# dimmer.net
KiCad netlist of a schematic drawn in EAGLE
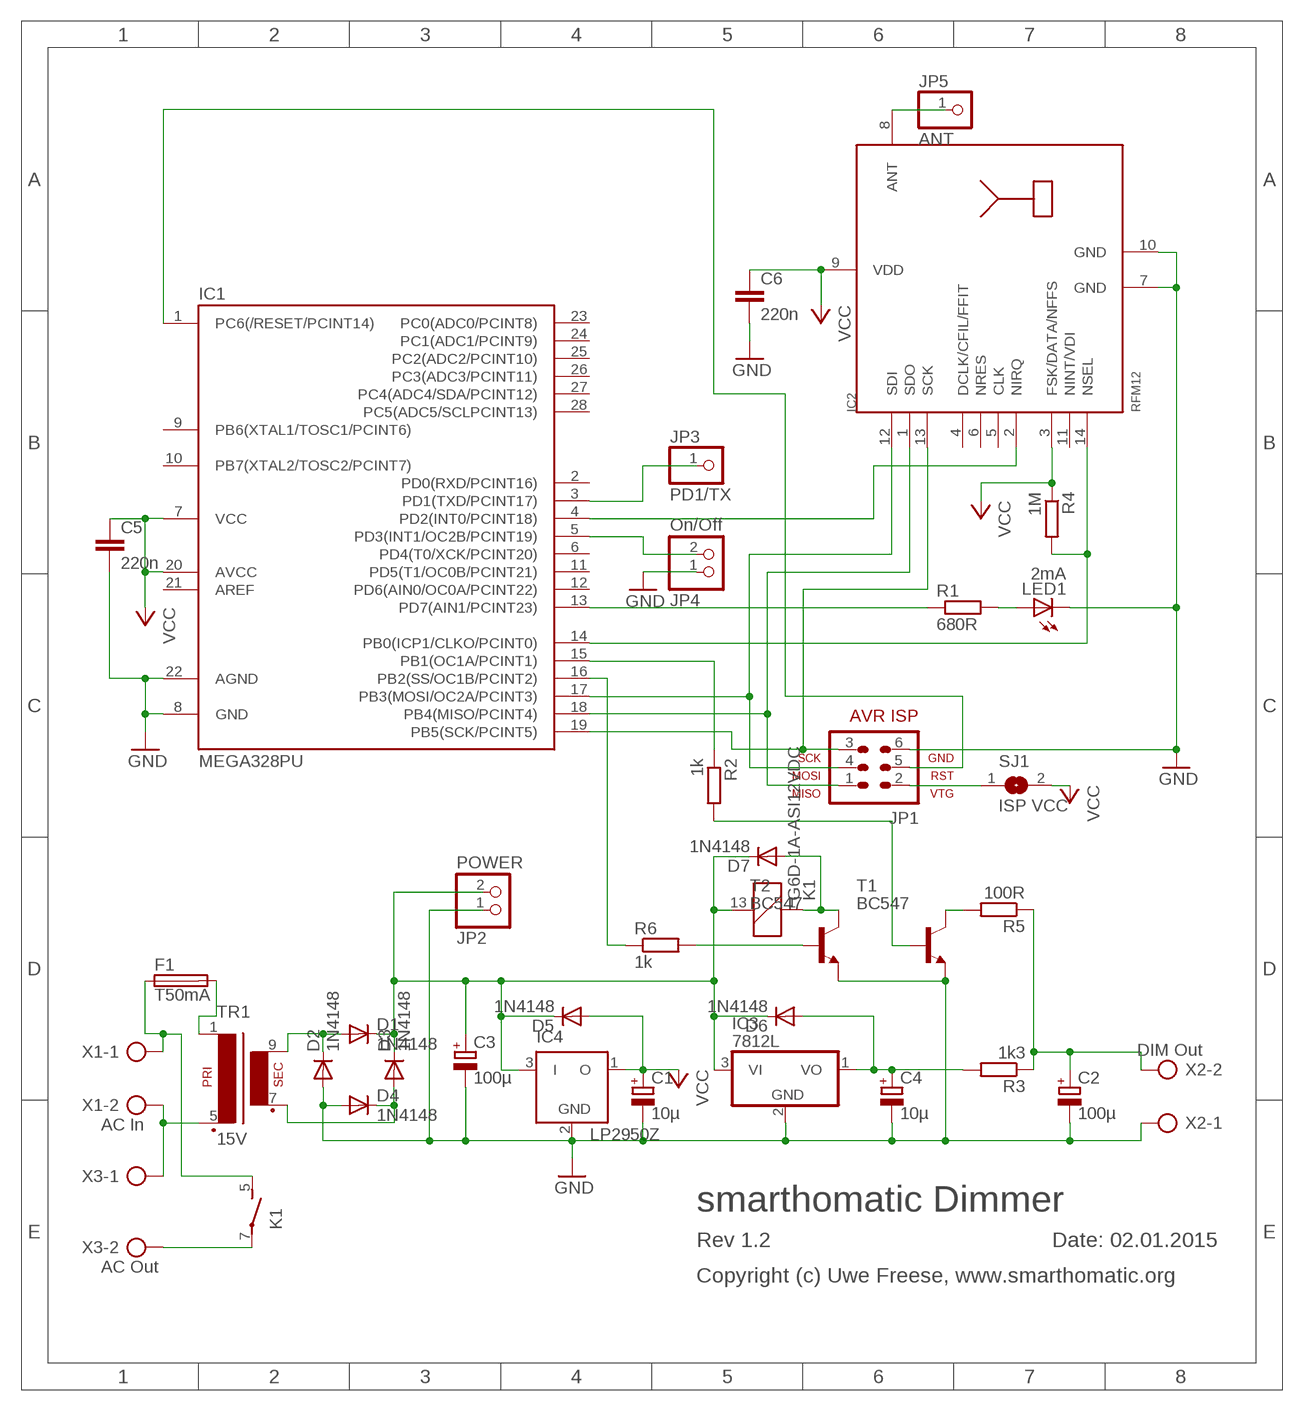
[diagram p0: schematic, sheet 1]

(export (version "E")
  (design (tool "Eeschema 10.0.6"))
  (components
    (comp (ref "C1")
      (value "10µ")
      (footprint "eagle-import:E1,8-4")
      (libsource (lib "eagle-import") (part "CPOL-EUE1.8-4"))
    )
    (comp (ref "C2")
      (value "100µ")
      (footprint "eagle-import:E1,8-4")
      (libsource (lib "eagle-import") (part "CPOL-EUE1.8-4"))
    )
    (comp (ref "C3")
      (value "100µ")
      (footprint "eagle-import:E1,8-4")
      (libsource (lib "eagle-import") (part "CPOL-EUE1.8-4"))
    )
    (comp (ref "C4")
      (value "10µ")
      (footprint "eagle-import:E1,8-4")
      (libsource (lib "eagle-import") (part "CPOL-EUE1.8-4"))
    )
    (comp (ref "C5")
      (value "220n")
      (footprint "eagle-import:C2.5-3")
      (libsource (lib "eagle-import") (part "C2,5-3"))
    )
    (comp (ref "C6")
      (value "220n")
      (footprint "eagle-import:C2.5-3")
      (libsource (lib "eagle-import") (part "C2,5-3"))
    )
    (comp (ref "D1")
      (value "1N4148")
      (footprint "eagle-import:DO35-7")
      (libsource (lib "eagle-import") (part "1N4148DO35-7"))
    )
    (comp (ref "D2")
      (value "1N4148")
      (footprint "eagle-import:DO35-7")
      (libsource (lib "eagle-import") (part "1N4148DO35-7"))
    )
    (comp (ref "D3")
      (value "1N4148")
      (footprint "eagle-import:DO35-7")
      (libsource (lib "eagle-import") (part "1N4148DO35-7"))
    )
    (comp (ref "D4")
      (value "1N4148")
      (footprint "eagle-import:DO35-7")
      (libsource (lib "eagle-import") (part "1N4148DO35-7"))
    )
    (comp (ref "D5")
      (value "1N4148")
      (footprint "eagle-import:DO35-7")
      (libsource (lib "eagle-import") (part "1N4148DO35-7"))
    )
    (comp (ref "D6")
      (value "1N4148")
      (footprint "eagle-import:DO35-7")
      (libsource (lib "eagle-import") (part "1N4148DO35-7"))
    )
    (comp (ref "D7")
      (value "1N4148")
      (footprint "eagle-import:DO35-7")
      (libsource (lib "eagle-import") (part "1N4148DO35-7"))
    )
    (comp (ref "F1")
      (value "T50mA")
      (footprint "eagle-import:SH22,5")
      (fields (field (name "MF") "SCHURTER") (field (name "MPN") "0031.8201"))
      (libsource (lib "eagle-import") (part "SH22,5"))
    )
    (comp (ref "IC1")
      (value "MEGA328PU")
      (footprint "eagle-import:DIL28-3")
      (libsource (lib "eagle-import") (part "MEGA48/88/168-PU"))
    )
    (comp (ref "IC2")
      (value "RFM12")
      (footprint "eagle-import:RFM")
      (libsource (lib "eagle-import") (part "RFM12"))
    )
    (comp (ref "IC3")
      (value "7812L")
      (footprint "eagle-import:TO92")
      (libsource (lib "eagle-import") (part "78L12"))
    )
    (comp (ref "IC4")
      (value "LP2950Z")
      (footprint "eagle-import:TO92")
      (libsource (lib "eagle-import") (part "LP2950Z"))
    )
    (comp (ref "JP1")
      (value "AVR-ISP-6")
      (footprint "eagle-import:AVR-ISP-6")
      (libsource (lib "eagle-import") (part "AVR-ISP-6"))
    )
    (comp (ref "JP2")
      (value "POWER")
      (footprint "eagle-import:1X02")
      (libsource (lib "eagle-import") (part "PINHD-1X2"))
    )
    (comp (ref "JP3")
      (value "PD1/TX")
      (footprint "eagle-import:1X01")
      (libsource (lib "eagle-import") (part "PINHD-1X1"))
    )
    (comp (ref "JP4")
      (value "On/Off")
      (footprint "eagle-import:1X02")
      (libsource (lib "eagle-import") (part "PINHD-1X2"))
    )
    (comp (ref "JP5")
      (value "ANT")
      (footprint "eagle-import:1X01")
      (libsource (lib "eagle-import") (part "PINHD-1X1"))
    )
    (comp (ref "K1")
      (value "G6D-1A-ASI12VDC")
      (footprint "eagle-import:G6D")
      (libsource (lib "eagle-import") (part "G6D?-1A-ASI12VDC"))
    )
    (comp (ref "LED1")
      (value "2mA")
      (footprint "eagle-import:LED3MM")
      (libsource (lib "eagle-import") (part "LED3MM"))
    )
    (comp (ref "R1")
      (value "680R")
      (footprint "eagle-import:0207_7")
      (libsource (lib "eagle-import") (part "R-EU_0207/7"))
    )
    (comp (ref "R2")
      (value "1k")
      (footprint "eagle-import:0207_7")
      (libsource (lib "eagle-import") (part "R-EU_0207/7"))
    )
    (comp (ref "R3")
      (value "1k3")
      (footprint "eagle-import:0207_7")
      (libsource (lib "eagle-import") (part "R-EU_0207/7"))
    )
    (comp (ref "R4")
      (value "1M")
      (footprint "eagle-import:0207_7")
      (libsource (lib "eagle-import") (part "R-EU_0207/7"))
    )
    (comp (ref "R5")
      (value "100R")
      (footprint "eagle-import:0207_7")
      (libsource (lib "eagle-import") (part "R-EU_0207/7"))
    )
    (comp (ref "R6")
      (value "1k")
      (footprint "eagle-import:0207_7")
      (libsource (lib "eagle-import") (part "R-EU_0207/7"))
    )
    (comp (ref "SJ1")
      (value "ISP VCC")
      (footprint "eagle-import:SJ")
      (libsource (lib "eagle-import") (part "SJ"))
    )
    (comp (ref "T1")
      (value "BC547")
      (footprint "eagle-import:TO92")
      (libsource (lib "eagle-import") (part "BC547"))
    )
    (comp (ref "T2")
      (value "BC547")
      (footprint "eagle-import:TO92")
      (libsource (lib "eagle-import") (part "BC547"))
    )
    (comp (ref "TR1")
      (value "15V")
      (footprint "eagle-import:EI30-1")
      (libsource (lib "eagle-import") (part "EI30-1"))
    )
    (comp (ref "X1")
      (value "AC In")
      (footprint "eagle-import:AK500_2")
      (libsource (lib "eagle-import") (part "AK500/2"))
    )
    (comp (ref "X2")
      (value "DIM Out")
      (footprint "eagle-import:AK500_2")
      (libsource (lib "eagle-import") (part "AK500/2"))
    )
    (comp (ref "X3")
      (value "AC Out")
      (footprint "eagle-import:AK500_2")
      (fields (field (name "OC_FARNELL") "unknown") (field (name "OC_NEWARK") "unknown"))
      (libsource (lib "eagle-import") (part "AK500/2"))
    )
  )
  (nets
    (net (code "1") (name "GND") (class "Default")
      (node (ref "C1") (pin "-") (pinfunction "-_-") (pintype "passive"))
      (node (ref "C2") (pin "-") (pinfunction "-_-") (pintype "passive"))
      (node (ref "C3") (pin "-") (pinfunction "-_-") (pintype "passive"))
      (node (ref "C4") (pin "-") (pinfunction "-_-") (pintype "passive"))
      (node (ref "C5") (pin "2") (pinfunction "2_2") (pintype "passive"))
      (node (ref "C6") (pin "2") (pinfunction "2_2") (pintype "passive"))
      (node (ref "D2") (pin "A") (pinfunction "A_A") (pintype "passive"))
      (node (ref "D4") (pin "A") (pinfunction "A_A") (pintype "passive"))
      (node (ref "IC1") (pin "22") (pinfunction "AGND_22") (pintype "power_in"))
      (node (ref "IC1") (pin "8") (pinfunction "GND_8") (pintype "power_in"))
      (node (ref "IC2") (pin "10") (pinfunction "GND_10") (pintype "power_in"))
      (node (ref "IC2") (pin "7") (pinfunction "GND_7") (pintype "power_in"))
      (node (ref "IC3") (pin "2") (pinfunction "GND_2") (pintype "passive"))
      (node (ref "IC4") (pin "2") (pinfunction "GND_2") (pintype "power_in"))
      (node (ref "JP1") (pin "6") (pinfunction "6_6") (pintype "passive"))
      (node (ref "JP2") (pin "1") (pinfunction "1_1") (pintype "passive"))
      (node (ref "JP4") (pin "1") (pinfunction "1_1") (pintype "passive"))
      (node (ref "LED1") (pin "K") (pinfunction "C_K") (pintype "passive"))
      (node (ref "T1") (pin "1") (pinfunction "E_1") (pintype "passive"))
      (node (ref "T2") (pin "1") (pinfunction "E_1") (pintype "passive"))
      (node (ref "X2") (pin "1") (pinfunction "KL_1") (pintype "passive"))
    )
    (net (code "2") (name "Net-(IC1-PB0(ICP1{slash}CLKO{slash}PCINT0))") (class "Default")
      (node (ref "IC1") (pin "14") (pinfunction "PB0(ICP1/CLKO/PCINT0)_14") (pintype "bidirectional"))
      (node (ref "IC2") (pin "14") (pinfunction "NSEL_14") (pintype "bidirectional"))
      (node (ref "R4") (pin "2") (pinfunction "2_2") (pintype "passive"))
    )
    (net (code "3") (name "Net-(IC1-PB1(OC1A{slash}PCINT1))") (class "Default")
      (node (ref "IC1") (pin "15") (pinfunction "PB1(OC1A/PCINT1)_15") (pintype "bidirectional"))
      (node (ref "R2") (pin "1") (pinfunction "1_1") (pintype "passive"))
    )
    (net (code "4") (name "Net-(IC1-PB2(SS{slash}OC1B{slash}PCINT2))") (class "Default")
      (node (ref "IC1") (pin "16") (pinfunction "PB2(SS/OC1B/PCINT2)_16") (pintype "bidirectional"))
      (node (ref "R6") (pin "1") (pinfunction "1_1") (pintype "passive"))
    )
    (net (code "5") (name "Net-(IC1-PB3(MOSI{slash}OC2A{slash}PCINT3))") (class "Default")
      (node (ref "IC1") (pin "17") (pinfunction "PB3(MOSI/OC2A/PCINT3)_17") (pintype "bidirectional"))
      (node (ref "IC2") (pin "12") (pinfunction "SDI_12") (pintype "bidirectional"))
      (node (ref "JP1") (pin "4") (pinfunction "4_4") (pintype "passive"))
    )
    (net (code "6") (name "Net-(IC1-PB4(MISO{slash}PCINT4))") (class "Default")
      (node (ref "IC1") (pin "18") (pinfunction "PB4(MISO/PCINT4)_18") (pintype "bidirectional"))
      (node (ref "IC2") (pin "1") (pinfunction "SDO_1") (pintype "bidirectional"))
      (node (ref "JP1") (pin "1") (pinfunction "1_1") (pintype "passive"))
    )
    (net (code "7") (name "Net-(IC1-PB5(SCK{slash}PCINT5))") (class "Default")
      (node (ref "IC1") (pin "19") (pinfunction "PB5(SCK/PCINT5)_19") (pintype "bidirectional"))
      (node (ref "IC2") (pin "13") (pinfunction "SCK_13") (pintype "bidirectional"))
      (node (ref "JP1") (pin "3") (pinfunction "3_3") (pintype "passive"))
    )
    (net (code "8") (name "Net-(IC1-PC6({slash}RESET{slash}PCINT14))") (class "Default")
      (node (ref "IC1") (pin "1") (pinfunction "PC6(/RESET/PCINT14)_1") (pintype "bidirectional"))
      (node (ref "JP1") (pin "5") (pinfunction "5_5") (pintype "passive"))
    )
    (net (code "9") (name "Net-(IC1-PD1(TXD{slash}PCINT17))") (class "Default")
      (node (ref "IC1") (pin "3") (pinfunction "PD1(TXD/PCINT17)_3") (pintype "bidirectional"))
      (node (ref "JP3") (pin "1") (pinfunction "1_1") (pintype "passive"))
    )
    (net (code "10") (name "Net-(IC1-PD2(INT0{slash}PCINT18))") (class "Default")
      (node (ref "IC1") (pin "4") (pinfunction "PD2(INT0/PCINT18)_4") (pintype "bidirectional"))
      (node (ref "IC2") (pin "2") (pinfunction "NIRQ_2") (pintype "bidirectional"))
    )
    (net (code "11") (name "Net-(IC1-PD3(INT1{slash}OC2B{slash}PCINT19))") (class "Default")
      (node (ref "IC1") (pin "5") (pinfunction "PD3(INT1/OC2B/PCINT19)_5") (pintype "bidirectional"))
      (node (ref "JP4") (pin "2") (pinfunction "2_2") (pintype "passive"))
    )
    (net (code "12") (name "Net-(IC1-PD7(AIN1{slash}PCINT23))") (class "Default")
      (node (ref "IC1") (pin "13") (pinfunction "PD7(AIN1/PCINT23)_13") (pintype "bidirectional"))
      (node (ref "R1") (pin "1") (pinfunction "1_1") (pintype "passive"))
    )
    (net (code "13") (name "Net-(IC2-ANT)") (class "Default")
      (node (ref "IC2") (pin "8") (pinfunction "ANT_8") (pintype "output"))
      (node (ref "JP5") (pin "1") (pinfunction "1_1") (pintype "passive"))
    )
    (net (code "14") (name "Net-(IC3-VI)") (class "Default")
      (node (ref "C3") (pin "+") (pinfunction "+_+") (pintype "passive"))
      (node (ref "D1") (pin "C") (pinfunction "C_C") (pintype "passive"))
      (node (ref "D3") (pin "C") (pinfunction "C_C") (pintype "passive"))
      (node (ref "D5") (pin "C") (pinfunction "C_C") (pintype "passive"))
      (node (ref "D6") (pin "C") (pinfunction "C_C") (pintype "passive"))
      (node (ref "D7") (pin "C") (pinfunction "C_C") (pintype "passive"))
      (node (ref "IC3") (pin "3") (pinfunction "VI_3") (pintype "input"))
      (node (ref "IC4") (pin "3") (pinfunction "I_3") (pintype "input"))
      (node (ref "JP2") (pin "2") (pinfunction "2_2") (pintype "passive"))
      (node (ref "K1") (pin "13") (pinfunction "2_13") (pintype "passive"))
    )
    (net (code "15") (name "Net-(IC3-VO)") (class "Default")
      (node (ref "C4") (pin "+") (pinfunction "+_+") (pintype "passive"))
      (node (ref "D6") (pin "A") (pinfunction "A_A") (pintype "passive"))
      (node (ref "IC3") (pin "1") (pinfunction "VO_1") (pintype "passive"))
      (node (ref "R3") (pin "2") (pinfunction "2_2") (pintype "passive"))
    )
    (net (code "16") (name "Net-(JP1-Pad2)") (class "Default")
      (node (ref "JP1") (pin "2") (pinfunction "2_2") (pintype "passive"))
      (node (ref "SJ1") (pin "1") (pinfunction "1_1") (pintype "passive"))
    )
    (net (code "17") (name "Net-(K1B-P)") (class "Default")
      (node (ref "K1") (pin "7") (pinfunction "P_7") (pintype "passive"))
      (node (ref "X3") (pin "2") (pinfunction "KL_2") (pintype "passive"))
    )
    (net (code "18") (name "Net-(K1B-S)") (class "Default")
      (node (ref "F1") (pin "1") (pinfunction "1_1") (pintype "passive"))
      (node (ref "K1") (pin "5") (pinfunction "S_5") (pintype "passive"))
      (node (ref "X1") (pin "1") (pinfunction "KL_1") (pintype "passive"))
    )
    (net (code "19") (name "Net-(LED1-PadA)") (class "Default")
      (node (ref "LED1") (pin "A") (pinfunction "A_A") (pintype "passive"))
      (node (ref "R1") (pin "2") (pinfunction "2_2") (pintype "passive"))
    )
    (net (code "20") (name "Net-(T1-B)") (class "Default")
      (node (ref "R2") (pin "2") (pinfunction "2_2") (pintype "passive"))
      (node (ref "T1") (pin "2") (pinfunction "B_2") (pintype "passive"))
    )
    (net (code "21") (name "Net-(T1-C)") (class "Default")
      (node (ref "R5") (pin "2") (pinfunction "2_2") (pintype "passive"))
      (node (ref "T1") (pin "3") (pinfunction "C_3") (pintype "passive"))
    )
    (net (code "22") (name "Net-(T2-B)") (class "Default")
      (node (ref "R6") (pin "2") (pinfunction "2_2") (pintype "passive"))
      (node (ref "T2") (pin "2") (pinfunction "B_2") (pintype "passive"))
    )
    (net (code "23") (name "Net-(T2-C)") (class "Default")
      (node (ref "D7") (pin "A") (pinfunction "A_A") (pintype "passive"))
      (node (ref "K1") (pin "1") (pinfunction "1_1") (pintype "passive"))
      (node (ref "T2") (pin "3") (pinfunction "C_3") (pintype "passive"))
    )
    (net (code "24") (name "Net-(TR1-P1)") (class "Default")
      (node (ref "F1") (pin "2") (pinfunction "2_2") (pintype "passive"))
      (node (ref "TR1") (pin "1") (pinfunction "P1_1") (pintype "passive"))
    )
    (net (code "25") (name "Net-(TR1-P2)") (class "Default")
      (node (ref "TR1") (pin "5") (pinfunction "P2_5") (pintype "passive"))
      (node (ref "X1") (pin "2") (pinfunction "KL_2") (pintype "passive"))
      (node (ref "X3") (pin "1") (pinfunction "KL_1") (pintype "passive"))
    )
    (net (code "26") (name "Net-(TR1-S3)") (class "Default")
      (node (ref "D3") (pin "A") (pinfunction "A_A") (pintype "passive"))
      (node (ref "D4") (pin "C") (pinfunction "C_C") (pintype "passive"))
      (node (ref "TR1") (pin "7") (pinfunction "S3_7") (pintype "passive"))
    )
    (net (code "27") (name "Net-(TR1-S4)") (class "Default")
      (node (ref "D1") (pin "A") (pinfunction "A_A") (pintype "passive"))
      (node (ref "D2") (pin "C") (pinfunction "C_C") (pintype "passive"))
      (node (ref "TR1") (pin "9") (pinfunction "S4_9") (pintype "passive"))
    )
    (net (code "28") (name "Net-(X2B-KL)") (class "Default")
      (node (ref "C2") (pin "+") (pinfunction "+_+") (pintype "passive"))
      (node (ref "R3") (pin "1") (pinfunction "1_1") (pintype "passive"))
      (node (ref "R5") (pin "1") (pinfunction "1_1") (pintype "passive"))
      (node (ref "X2") (pin "2") (pinfunction "KL_2") (pintype "passive"))
    )
    (net (code "29") (name "VCC") (class "Default")
      (node (ref "C1") (pin "+") (pinfunction "+_+") (pintype "passive"))
      (node (ref "C5") (pin "1") (pinfunction "1_1") (pintype "passive"))
      (node (ref "C6") (pin "1") (pinfunction "1_1") (pintype "passive"))
      (node (ref "D5") (pin "A") (pinfunction "A_A") (pintype "passive"))
      (node (ref "IC1") (pin "20") (pinfunction "AVCC_20") (pintype "passive"))
      (node (ref "IC1") (pin "7") (pinfunction "VCC_7") (pintype "power_in"))
      (node (ref "IC2") (pin "3") (pinfunction "FSK/DATA/NFFS_3") (pintype "bidirectional"))
      (node (ref "IC2") (pin "9") (pinfunction "VDD_9") (pintype "power_in"))
      (node (ref "IC4") (pin "1") (pinfunction "O_1") (pintype "input"))
      (node (ref "R4") (pin "1") (pinfunction "1_1") (pintype "passive"))
      (node (ref "SJ1") (pin "2") (pinfunction "2_2") (pintype "passive"))
    )
    (net (code "30") (name "unconnected-(IC1-AREF-Pad21)") (class "Default")
      (node (ref "IC1") (pin "21") (pinfunction "AREF_21") (pintype "passive"))
    )
    (net (code "31") (name "unconnected-(IC1-PB6(XTAL1{slash}TOSC1{slash}PCINT6)-Pad9)") (class "Default")
      (node (ref "IC1") (pin "9") (pinfunction "PB6(XTAL1/TOSC1/PCINT6)_9") (pintype "bidirectional"))
    )
    (net (code "32") (name "unconnected-(IC1-PB7(XTAL2{slash}TOSC2{slash}PCINT7)-Pad10)") (class "Default")
      (node (ref "IC1") (pin "10") (pinfunction "PB7(XTAL2/TOSC2/PCINT7)_10") (pintype "bidirectional"))
    )
    (net (code "33") (name "unconnected-(IC1-PC0(ADC0{slash}PCINT8)-Pad23)") (class "Default")
      (node (ref "IC1") (pin "23") (pinfunction "PC0(ADC0/PCINT8)_23") (pintype "bidirectional"))
    )
    (net (code "34") (name "unconnected-(IC1-PC1(ADC1{slash}PCINT9)-Pad24)") (class "Default")
      (node (ref "IC1") (pin "24") (pinfunction "PC1(ADC1/PCINT9)_24") (pintype "bidirectional"))
    )
    (net (code "35") (name "unconnected-(IC1-PC2(ADC2{slash}PCINT10)-Pad25)") (class "Default")
      (node (ref "IC1") (pin "25") (pinfunction "PC2(ADC2/PCINT10)_25") (pintype "bidirectional"))
    )
    (net (code "36") (name "unconnected-(IC1-PC3(ADC3{slash}PCINT11)-Pad26)") (class "Default")
      (node (ref "IC1") (pin "26") (pinfunction "PC3(ADC3/PCINT11)_26") (pintype "bidirectional"))
    )
    (net (code "37") (name "unconnected-(IC1-PC4(ADC4{slash}SDA{slash}PCINT12)-Pad27)") (class "Default")
      (node (ref "IC1") (pin "27") (pinfunction "PC4(ADC4/SDA/PCINT12)_27") (pintype "bidirectional"))
    )
    (net (code "38") (name "unconnected-(IC1-PC5(ADC5{slash}SCLPCINT13)-Pad28)") (class "Default")
      (node (ref "IC1") (pin "28") (pinfunction "PC5(ADC5/SCLPCINT13)_28") (pintype "bidirectional"))
    )
    (net (code "39") (name "unconnected-(IC1-PD0(RXD{slash}PCINT16)-Pad2)") (class "Default")
      (node (ref "IC1") (pin "2") (pinfunction "PD0(RXD/PCINT16)_2") (pintype "bidirectional"))
    )
    (net (code "40") (name "unconnected-(IC1-PD4(T0{slash}XCK{slash}PCINT20)-Pad6)") (class "Default")
      (node (ref "IC1") (pin "6") (pinfunction "PD4(T0/XCK/PCINT20)_6") (pintype "bidirectional"))
    )
    (net (code "41") (name "unconnected-(IC1-PD5(T1{slash}OC0B{slash}PCINT21)-Pad11)") (class "Default")
      (node (ref "IC1") (pin "11") (pinfunction "PD5(T1/OC0B/PCINT21)_11") (pintype "bidirectional"))
    )
    (net (code "42") (name "unconnected-(IC1-PD6(AIN0{slash}OC0A{slash}PCINT22)-Pad12)") (class "Default")
      (node (ref "IC1") (pin "12") (pinfunction "PD6(AIN0/OC0A/PCINT22)_12") (pintype "bidirectional"))
    )
    (net (code "43") (name "unconnected-(IC2-CLK-Pad5)") (class "Default")
      (node (ref "IC2") (pin "5") (pinfunction "CLK_5") (pintype "bidirectional"))
    )
    (net (code "44") (name "unconnected-(IC2-DCLK{slash}CFIL{slash}FFIT-Pad4)") (class "Default")
      (node (ref "IC2") (pin "4") (pinfunction "DCLK/CFIL/FFIT_4") (pintype "bidirectional"))
    )
    (net (code "45") (name "unconnected-(IC2-NINT{slash}VDI-Pad11)") (class "Default")
      (node (ref "IC2") (pin "11") (pinfunction "NINT/VDI_11") (pintype "bidirectional"))
    )
    (net (code "46") (name "unconnected-(IC2-NRES-Pad6)") (class "Default")
      (node (ref "IC2") (pin "6") (pinfunction "NRES_6") (pintype "bidirectional"))
    )
  )
)
